# FARv1.net
KiCad netlist of a schematic drawn in EAGLE
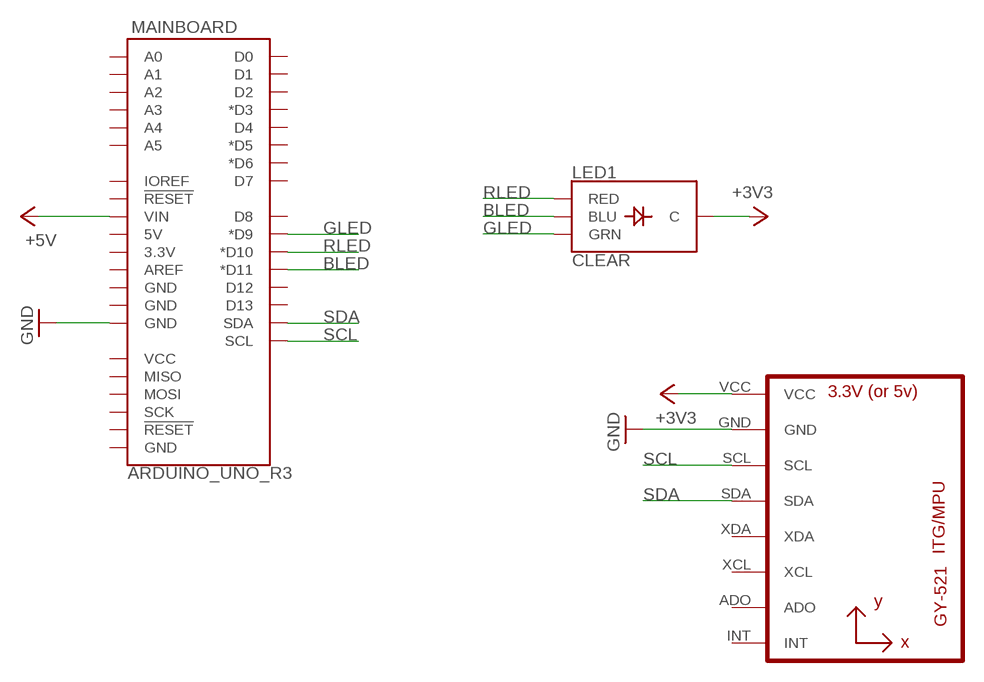
[diagram p0: schematic, sheet 1]

(export (version "E")
  (design (tool "Eeschema 10.0.6"))
  (components
    (comp (ref "LED1")
      (value "CLEAR")
      (footprint "eagle-import:LED-RGB-THRU")
      (libsource (lib "eagle-import") (part "LED-RGB-CCCLEAR"))
    )
    (comp (ref "MAINBOARD")
      (value "ARDUINO_UNO_R3")
      (footprint "eagle-import:ARDUINO_R3")
      (libsource (lib "eagle-import") (part "ARDUINO_UNO_R3"))
    )
    (comp (ref "U1")
      (value "GY-521MPU6050")
      (footprint "eagle-import:GY-521")
      (libsource (lib "eagle-import") (part "GY-521MPU6050"))
    )
  )
  (nets
    (net (code "1") (name "+3V3") (class "Default")
      (node (ref "LED1") (pin "2") (pinfunction "C_2") (pintype "bidirectional"))
      (node (ref "U1") (pin "VCC") (pinfunction "VCC_VCC") (pintype "bidirectional"))
    )
    (net (code "2") (name "+5V") (class "Default")
      (node (ref "MAINBOARD") (pin "VIN") (pinfunction "VIN_VIN") (pintype "bidirectional"))
    )
    (net (code "3") (name "/BLED") (class "Default")
      (node (ref "LED1") (pin "4") (pinfunction "BLU_4") (pintype "bidirectional"))
      (node (ref "MAINBOARD") (pin "D11") (pinfunction "*D11_D11") (pintype "bidirectional"))
    )
    (net (code "4") (name "/GLED") (class "Default")
      (node (ref "LED1") (pin "3") (pinfunction "GRN_3") (pintype "bidirectional"))
      (node (ref "MAINBOARD") (pin "D9") (pinfunction "*D9_D9") (pintype "bidirectional"))
    )
    (net (code "5") (name "/RLED") (class "Default")
      (node (ref "LED1") (pin "1") (pinfunction "RED_1") (pintype "bidirectional"))
      (node (ref "MAINBOARD") (pin "D10") (pinfunction "*D10_D10") (pintype "bidirectional"))
    )
    (net (code "6") (name "/SCL") (class "Default")
      (node (ref "MAINBOARD") (pin "SCL") (pinfunction "SCL_SCL") (pintype "bidirectional"))
      (node (ref "U1") (pin "SCL") (pinfunction "SCL_SCL") (pintype "bidirectional"))
    )
    (net (code "7") (name "/SDA") (class "Default")
      (node (ref "MAINBOARD") (pin "SDA") (pinfunction "SDA_SDA") (pintype "bidirectional"))
      (node (ref "U1") (pin "SDA") (pinfunction "SDA_SDA") (pintype "bidirectional"))
    )
    (net (code "8") (name "GND") (class "Default")
      (node (ref "MAINBOARD") (pin "GND@2") (pinfunction "GND_GND@2") (pintype "bidirectional"))
      (node (ref "U1") (pin "GND") (pinfunction "GND_GND") (pintype "bidirectional"))
    )
    (net (code "9") (name "unconnected-(MAINBOARD-*D3-PadD3)") (class "Default")
      (node (ref "MAINBOARD") (pin "D3") (pinfunction "*D3_D3") (pintype "bidirectional"))
    )
    (net (code "10") (name "unconnected-(MAINBOARD-*D5-PadD5)") (class "Default")
      (node (ref "MAINBOARD") (pin "D5") (pinfunction "*D5_D5") (pintype "bidirectional"))
    )
    (net (code "11") (name "unconnected-(MAINBOARD-*D6-PadD6)") (class "Default")
      (node (ref "MAINBOARD") (pin "D6") (pinfunction "*D6_D6") (pintype "bidirectional"))
    )
    (net (code "12") (name "unconnected-(MAINBOARD-GND-PadGND@1)") (class "Default")
      (node (ref "MAINBOARD") (pin "GND@1") (pinfunction "GND_GND@1") (pintype "bidirectional"))
    )
    (net (code "13") (name "unconnected-(MAINBOARD-GND-PadGND@3)") (class "Default")
      (node (ref "MAINBOARD") (pin "GND@3") (pinfunction "GND_GND@3") (pintype "bidirectional"))
    )
    (net (code "14") (name "unconnected-(MAINBOARD-GND-PadGND@4)") (class "Default")
      (node (ref "MAINBOARD") (pin "GND@4") (pinfunction "GND_GND@4") (pintype "bidirectional"))
    )
    (net (code "15") (name "unconnected-(MAINBOARD-Pad3.3V)") (class "Default")
      (node (ref "MAINBOARD") (pin "3.3V") (pinfunction "3.3V_3.3V") (pintype "bidirectional"))
    )
    (net (code "16") (name "unconnected-(MAINBOARD-Pad5V)") (class "Default")
      (node (ref "MAINBOARD") (pin "5V") (pinfunction "5V_5V") (pintype "bidirectional"))
    )
    (net (code "17") (name "unconnected-(MAINBOARD-PadA0)") (class "Default")
      (node (ref "MAINBOARD") (pin "A0") (pinfunction "A0_A0") (pintype "bidirectional"))
    )
    (net (code "18") (name "unconnected-(MAINBOARD-PadA1)") (class "Default")
      (node (ref "MAINBOARD") (pin "A1") (pinfunction "A1_A1") (pintype "bidirectional"))
    )
    (net (code "19") (name "unconnected-(MAINBOARD-PadA2)") (class "Default")
      (node (ref "MAINBOARD") (pin "A2") (pinfunction "A2_A2") (pintype "bidirectional"))
    )
    (net (code "20") (name "unconnected-(MAINBOARD-PadA3)") (class "Default")
      (node (ref "MAINBOARD") (pin "A3") (pinfunction "A3_A3") (pintype "bidirectional"))
    )
    (net (code "21") (name "unconnected-(MAINBOARD-PadA4)") (class "Default")
      (node (ref "MAINBOARD") (pin "A4") (pinfunction "A4_A4") (pintype "bidirectional"))
    )
    (net (code "22") (name "unconnected-(MAINBOARD-PadA5)") (class "Default")
      (node (ref "MAINBOARD") (pin "A5") (pinfunction "A5_A5") (pintype "bidirectional"))
    )
    (net (code "23") (name "unconnected-(MAINBOARD-PadAREF)") (class "Default")
      (node (ref "MAINBOARD") (pin "AREF") (pinfunction "AREF_AREF") (pintype "bidirectional"))
    )
    (net (code "24") (name "unconnected-(MAINBOARD-PadD0)") (class "Default")
      (node (ref "MAINBOARD") (pin "D0") (pinfunction "D0_D0") (pintype "bidirectional"))
    )
    (net (code "25") (name "unconnected-(MAINBOARD-PadD1)") (class "Default")
      (node (ref "MAINBOARD") (pin "D1") (pinfunction "D1_D1") (pintype "bidirectional"))
    )
    (net (code "26") (name "unconnected-(MAINBOARD-PadD2)") (class "Default")
      (node (ref "MAINBOARD") (pin "D2") (pinfunction "D2_D2") (pintype "bidirectional"))
    )
    (net (code "27") (name "unconnected-(MAINBOARD-PadD4)") (class "Default")
      (node (ref "MAINBOARD") (pin "D4") (pinfunction "D4_D4") (pintype "bidirectional"))
    )
    (net (code "28") (name "unconnected-(MAINBOARD-PadD7)") (class "Default")
      (node (ref "MAINBOARD") (pin "D7") (pinfunction "D7_D7") (pintype "bidirectional"))
    )
    (net (code "29") (name "unconnected-(MAINBOARD-PadD8)") (class "Default")
      (node (ref "MAINBOARD") (pin "D8") (pinfunction "D8_D8") (pintype "bidirectional"))
    )
    (net (code "30") (name "unconnected-(MAINBOARD-PadD12)") (class "Default")
      (node (ref "MAINBOARD") (pin "D12") (pinfunction "D12_D12") (pintype "bidirectional"))
    )
    (net (code "31") (name "unconnected-(MAINBOARD-PadD13)") (class "Default")
      (node (ref "MAINBOARD") (pin "D13") (pinfunction "D13_D13") (pintype "bidirectional"))
    )
    (net (code "32") (name "unconnected-(MAINBOARD-PadIOREF)") (class "Default")
      (node (ref "MAINBOARD") (pin "IOREF") (pinfunction "IOREF_IOREF") (pintype "bidirectional"))
    )
    (net (code "33") (name "unconnected-(MAINBOARD-PadMISO)") (class "Default")
      (node (ref "MAINBOARD") (pin "MISO") (pinfunction "MISO_MISO") (pintype "bidirectional"))
    )
    (net (code "34") (name "unconnected-(MAINBOARD-PadMOSI)") (class "Default")
      (node (ref "MAINBOARD") (pin "MOSI") (pinfunction "MOSI_MOSI") (pintype "bidirectional"))
    )
    (net (code "35") (name "unconnected-(MAINBOARD-PadSCK)") (class "Default")
      (node (ref "MAINBOARD") (pin "SCK") (pinfunction "SCK_SCK") (pintype "bidirectional"))
    )
    (net (code "36") (name "unconnected-(MAINBOARD-PadVCC)") (class "Default")
      (node (ref "MAINBOARD") (pin "VCC") (pinfunction "VCC_VCC") (pintype "bidirectional"))
    )
    (net (code "37") (name "unconnected-(MAINBOARD-~{RESET}-PadRESET@1)") (class "Default")
      (node (ref "MAINBOARD") (pin "RESET@1") (pinfunction "~{RESET}_RESET@1") (pintype "bidirectional"))
    )
    (net (code "38") (name "unconnected-(MAINBOARD-~{RESET}-PadRESET@2)") (class "Default")
      (node (ref "MAINBOARD") (pin "RESET@2") (pinfunction "~{RESET}_RESET@2") (pintype "bidirectional"))
    )
    (net (code "39") (name "unconnected-(U1-PadADO)") (class "Default")
      (node (ref "U1") (pin "ADO") (pinfunction "ADO_ADO") (pintype "bidirectional"))
    )
    (net (code "40") (name "unconnected-(U1-PadINT)") (class "Default")
      (node (ref "U1") (pin "INT") (pinfunction "INT_INT") (pintype "bidirectional"))
    )
    (net (code "41") (name "unconnected-(U1-PadXCL)") (class "Default")
      (node (ref "U1") (pin "XCL") (pinfunction "XCL_XCL") (pintype "bidirectional"))
    )
    (net (code "42") (name "unconnected-(U1-PadXDA)") (class "Default")
      (node (ref "U1") (pin "XDA") (pinfunction "XDA_XDA") (pintype "bidirectional"))
    )
  )
)
